# Sheet2.net
KiCad netlist of a schematic drawn in Altium Designer
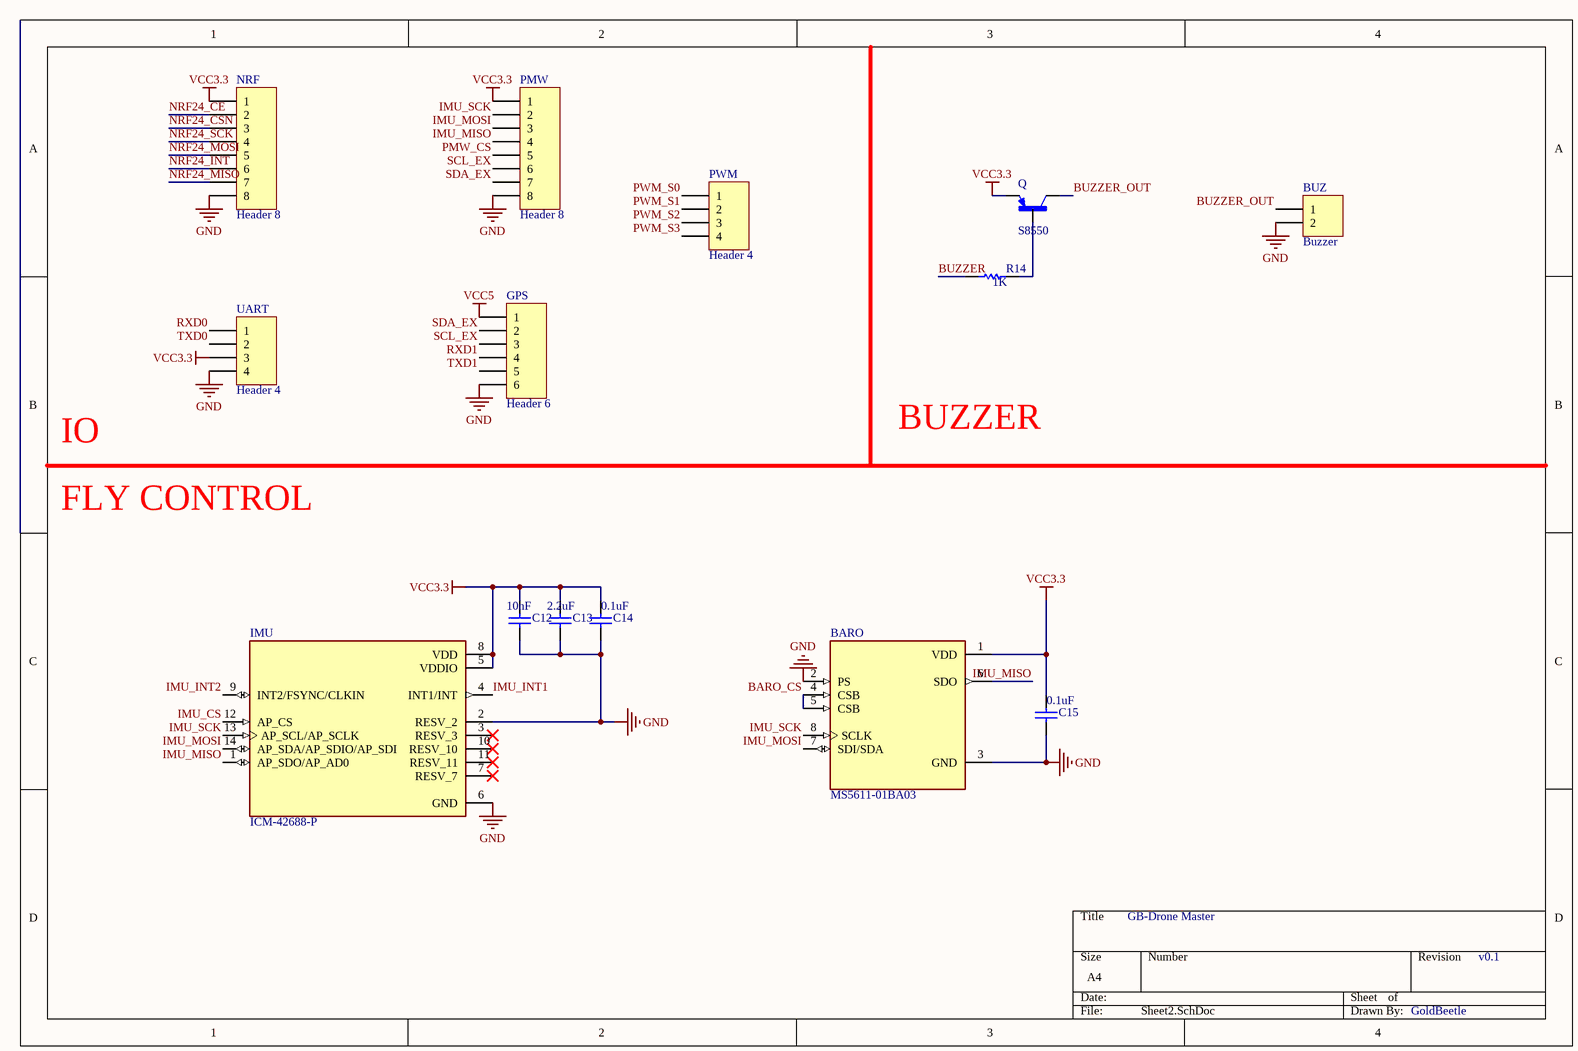
[diagram p0: Sheet2.SchDoc]

(export (version "E")
  (design (tool "Eeschema 10.0.6"))
  (components
    (comp (ref "BARO")
      (value "MS5611-01BA03")
      (footprint "MS5611-SON125P500X300X100-8N")
      (description "Pressure Sensor 0.15PSI ~ 17.4PSI (1kPa ~ 120kPa) Absolute - 24 b 8-SMD")
      (fields (field (name "MF") "TE Connectivity"))
      (libsource (lib "welkin_lib_v1.0") (part "MS5611-01BA03"))
    )
    (comp (ref "BUZ")
      (value "Buzzer")
      (footprint "POWER-2P")
      (description "Header, 2-Pin")
      (fields (field (name "PUBLISHER") "Altium Limited"))
      (libsource (lib "Miscellaneous Connectors") (part "Header 2"))
    )
    (comp (ref "C12")
      (value "10nF")
      (footprint "C0805")
      (description "Capacitor")
      (fields (field (name "Comment") "0.1uF/50V(10%)") (field (name "PUBLISHER") "Altium Limited"))
      (libsource (lib "Miscellaneous Devices") (part "Cap"))
    )
    (comp (ref "C13")
      (value "2.2uF")
      (footprint "C0805")
      (description "Capacitor")
      (fields (field (name "Comment") "10uF/25v(20%)") (field (name "PUBLISHER") "Altium Limited"))
      (libsource (lib "Miscellaneous Devices") (part "Cap"))
    )
    (comp (ref "C14")
      (value "0.1uF")
      (footprint "C0805")
      (description "Capacitor")
      (fields (field (name "Comment") "0.1uF/50V(10%)") (field (name "PUBLISHER") "Altium Limited"))
      (libsource (lib "Miscellaneous Devices") (part "Cap"))
    )
    (comp (ref "C15")
      (value "0.1uF")
      (footprint "C0805")
      (description "Capacitor")
      (fields (field (name "Comment") "0.1uF/50V(10%)") (field (name "PUBLISHER") "Altium Limited"))
      (libsource (lib "Miscellaneous Devices") (part "Cap"))
    )
    (comp (ref "GPS")
      (value "Header 6")
      (footprint "SIGNAL-6P")
      (description "Header, 6-Pin")
      (fields (field (name "PUBLISHER") "Altium Limited"))
      (libsource (lib "Miscellaneous Connectors") (part "Header 6"))
    )
    (comp (ref "IMU")
      (value "ICM-42688-P")
      (footprint "welkin_pcblib_v1.0:ICM42688-PQFN50P300X250X97-14N")
      (description "Accelerometer, Gyroscope, 6 Axis Sensor Output")
      (libsource (lib "welkin_lib_v1.0") (part "ICM-42688-P"))
    )
    (comp (ref "NRF")
      (value "Header 8")
      (footprint "SIGNAL-8P")
      (description "Header, 8-Pin")
      (fields (field (name "PUBLISHER") "Altium Limited"))
      (libsource (lib "Miscellaneous Connectors") (part "Header 8"))
    )
    (comp (ref "PMW")
      (value "Header 8")
      (footprint "SIGNAL-8P")
      (description "Header, 8-Pin")
      (fields (field (name "PUBLISHER") "Altium Limited"))
      (libsource (lib "Miscellaneous Connectors") (part "Header 8"))
    )
    (comp (ref "PWM")
      (value "Header 4")
      (footprint "SIGNAL-4P")
      (description "Header, 4-Pin")
      (fields (field (name "PUBLISHER") "Altium Limited"))
      (libsource (lib "Miscellaneous Connectors") (part "Header 4"))
    )
    (comp (ref "Q")
      (value "S8550")
      (footprint "SOT-23_S8550")
      (description "Bipolar (BJT) Transistor PNP 25 V 500 mA 150MHz 300 mW Surface Mount SOT-23")
      (fields (field (name "MF") "MDD"))
      (libsource (lib "welkin_lib_v1.0") (part "S8550"))
    )
    (comp (ref "R14")
      (value "1K")
      (footprint "C0805")
      (description "Resistor")
      (fields (field (name "PUBLISHER") "Altium Limited"))
      (libsource (lib "Miscellaneous Devices") (part "Res1"))
    )
    (comp (ref "UART")
      (value "Header 4")
      (footprint "HDR2X2")
      (description "Header, 4-Pin")
      (fields (field (name "PUBLISHER") "Altium Limited"))
      (libsource (lib "Miscellaneous Connectors") (part "Header 4"))
    )
  )
  (nets
    (net (code "1") (name "/BARO_CS") (class "Default")
      (node (ref "BARO") (pin "4") (pinfunction "CSB_4") (pintype "input"))
      (node (ref "BARO") (pin "5") (pinfunction "CSB_5") (pintype "input"))
    )
    (net (code "2") (name "/BUZZER") (class "Default")
      (node (ref "R14") (pin "1") (pinfunction "1_1") (pintype "passive"))
    )
    (net (code "3") (name "/BUZZER_OUT") (class "Default")
      (node (ref "BUZ") (pin "1") (pinfunction "1_1") (pintype "passive"))
      (node (ref "Q") (pin "3") (pinfunction "C_3") (pintype "passive"))
    )
    (net (code "4") (name "/IMU_CS") (class "Default")
      (node (ref "IMU") (pin "12") (pinfunction "AP_CS_12") (pintype "input"))
    )
    (net (code "5") (name "/IMU_INT1") (class "Default")
      (node (ref "IMU") (pin "4") (pinfunction "INT1/INT_4") (pintype "output"))
    )
    (net (code "6") (name "/IMU_INT2") (class "Default")
      (node (ref "IMU") (pin "9") (pinfunction "INT2/FSYNC/CLKIN_9") (pintype "bidirectional"))
    )
    (net (code "7") (name "/IMU_MISO") (class "Default")
      (node (ref "BARO") (pin "6") (pinfunction "SDO_6") (pintype "output"))
      (node (ref "IMU") (pin "1") (pinfunction "AP_SDO/AP_AD0_1") (pintype "bidirectional"))
      (node (ref "PMW") (pin "4") (pinfunction "4_4") (pintype "passive"))
    )
    (net (code "8") (name "/IMU_MOSI") (class "Default")
      (node (ref "BARO") (pin "7") (pinfunction "SDI/SDA_7") (pintype "bidirectional"))
      (node (ref "IMU") (pin "14") (pinfunction "AP_SDA/AP_SDIO/AP_SDI_14") (pintype "bidirectional"))
      (node (ref "PMW") (pin "3") (pinfunction "3_3") (pintype "passive"))
    )
    (net (code "9") (name "/IMU_SCK") (class "Default")
      (node (ref "BARO") (pin "8") (pinfunction "SCLK_8") (pintype "input"))
      (node (ref "IMU") (pin "13") (pinfunction "AP_SCL/AP_SCLK_13") (pintype "input"))
      (node (ref "PMW") (pin "2") (pinfunction "2_2") (pintype "passive"))
    )
    (net (code "10") (name "/NRF24_CE") (class "Default")
      (node (ref "NRF") (pin "2") (pinfunction "2_2") (pintype "passive"))
    )
    (net (code "11") (name "/NRF24_CSN") (class "Default")
      (node (ref "NRF") (pin "3") (pinfunction "3_3") (pintype "passive"))
    )
    (net (code "12") (name "/NRF24_INT") (class "Default")
      (node (ref "NRF") (pin "6") (pinfunction "6_6") (pintype "passive"))
    )
    (net (code "13") (name "/NRF24_MISO") (class "Default")
      (node (ref "NRF") (pin "7") (pinfunction "7_7") (pintype "passive"))
    )
    (net (code "14") (name "/NRF24_MOSI") (class "Default")
      (node (ref "NRF") (pin "5") (pinfunction "5_5") (pintype "passive"))
    )
    (net (code "15") (name "/NRF24_SCK") (class "Default")
      (node (ref "NRF") (pin "4") (pinfunction "4_4") (pintype "passive"))
    )
    (net (code "16") (name "/PMW_CS") (class "Default")
      (node (ref "PMW") (pin "5") (pinfunction "5_5") (pintype "passive"))
    )
    (net (code "17") (name "/PWM_S0") (class "Default")
      (node (ref "PWM") (pin "1") (pinfunction "1_1") (pintype "passive"))
    )
    (net (code "18") (name "/PWM_S1") (class "Default")
      (node (ref "PWM") (pin "2") (pinfunction "2_2") (pintype "passive"))
    )
    (net (code "19") (name "/PWM_S2") (class "Default")
      (node (ref "PWM") (pin "3") (pinfunction "3_3") (pintype "passive"))
    )
    (net (code "20") (name "/PWM_S3") (class "Default")
      (node (ref "PWM") (pin "4") (pinfunction "4_4") (pintype "passive"))
    )
    (net (code "21") (name "/RXD0") (class "Default")
      (node (ref "UART") (pin "1") (pinfunction "1_1") (pintype "passive"))
    )
    (net (code "22") (name "/RXD1") (class "Default")
      (node (ref "GPS") (pin "4") (pinfunction "4_4") (pintype "passive"))
    )
    (net (code "23") (name "/SCL_EX") (class "Default")
      (node (ref "GPS") (pin "3") (pinfunction "3_3") (pintype "passive"))
      (node (ref "PMW") (pin "6") (pinfunction "6_6") (pintype "passive"))
    )
    (net (code "24") (name "/SDA_EX") (class "Default")
      (node (ref "GPS") (pin "2") (pinfunction "2_2") (pintype "passive"))
      (node (ref "PMW") (pin "7") (pinfunction "7_7") (pintype "passive"))
    )
    (net (code "25") (name "/TXD0") (class "Default")
      (node (ref "UART") (pin "2") (pinfunction "2_2") (pintype "passive"))
    )
    (net (code "26") (name "/TXD1") (class "Default")
      (node (ref "GPS") (pin "5") (pinfunction "5_5") (pintype "passive"))
    )
    (net (code "27") (name "GND") (class "Default")
      (node (ref "BARO") (pin "2") (pinfunction "PS_2") (pintype "input"))
      (node (ref "BARO") (pin "3") (pinfunction "GND_3") (pintype "power_in"))
      (node (ref "BUZ") (pin "2") (pinfunction "2_2") (pintype "passive"))
      (node (ref "C12") (pin "2") (pinfunction "2_2") (pintype "passive"))
      (node (ref "C13") (pin "1") (pinfunction "1_1") (pintype "passive"))
      (node (ref "C14") (pin "2") (pinfunction "2_2") (pintype "passive"))
      (node (ref "C15") (pin "2") (pinfunction "2_2") (pintype "passive"))
      (node (ref "GPS") (pin "6") (pinfunction "6_6") (pintype "passive"))
      (node (ref "IMU") (pin "2") (pinfunction "RESV_2_2") (pintype "passive"))
      (node (ref "IMU") (pin "6") (pinfunction "GND_6") (pintype "power_in"))
      (node (ref "NRF") (pin "8") (pinfunction "8_8") (pintype "passive"))
      (node (ref "PMW") (pin "8") (pinfunction "8_8") (pintype "passive"))
      (node (ref "UART") (pin "4") (pinfunction "4_4") (pintype "passive"))
    )
    (net (code "28") (name "Net-(Q-B)") (class "Default")
      (node (ref "Q") (pin "1") (pinfunction "B_1") (pintype "passive"))
      (node (ref "R14") (pin "2") (pinfunction "2_2") (pintype "passive"))
    )
    (net (code "29") (name "VCC3.3") (class "Default")
      (node (ref "BARO") (pin "1") (pinfunction "VDD_1") (pintype "power_in"))
      (node (ref "C12") (pin "1") (pinfunction "1_1") (pintype "passive"))
      (node (ref "C13") (pin "2") (pinfunction "2_2") (pintype "passive"))
      (node (ref "C14") (pin "1") (pinfunction "1_1") (pintype "passive"))
      (node (ref "C15") (pin "1") (pinfunction "1_1") (pintype "passive"))
      (node (ref "IMU") (pin "5") (pinfunction "VDDIO_5") (pintype "power_in"))
      (node (ref "IMU") (pin "8") (pinfunction "VDD_8") (pintype "power_in"))
      (node (ref "NRF") (pin "1") (pinfunction "1_1") (pintype "passive"))
      (node (ref "PMW") (pin "1") (pinfunction "1_1") (pintype "passive"))
      (node (ref "Q") (pin "2") (pinfunction "E_2") (pintype "passive"))
      (node (ref "UART") (pin "3") (pinfunction "3_3") (pintype "passive"))
    )
    (net (code "30") (name "VCC5") (class "Default")
      (node (ref "GPS") (pin "1") (pinfunction "1_1") (pintype "passive"))
    )
    (net (code "31") (name "unconnected-(IMU-RESV_3-Pad3)") (class "Default")
      (node (ref "IMU") (pin "3") (pinfunction "RESV_3_3") (pintype "passive+no_connect"))
    )
    (net (code "32") (name "unconnected-(IMU-RESV_7-Pad7)") (class "Default")
      (node (ref "IMU") (pin "7") (pinfunction "RESV_7_7") (pintype "passive+no_connect"))
    )
    (net (code "33") (name "unconnected-(IMU-RESV_10-Pad10)") (class "Default")
      (node (ref "IMU") (pin "10") (pinfunction "RESV_10_10") (pintype "passive+no_connect"))
    )
    (net (code "34") (name "unconnected-(IMU-RESV_11-Pad11)") (class "Default")
      (node (ref "IMU") (pin "11") (pinfunction "RESV_11_11") (pintype "passive+no_connect"))
    )
  )
)
